# SAMC21_Xplained_Pro_EDBG.net
KiCad netlist of a schematic drawn in Altium Designer
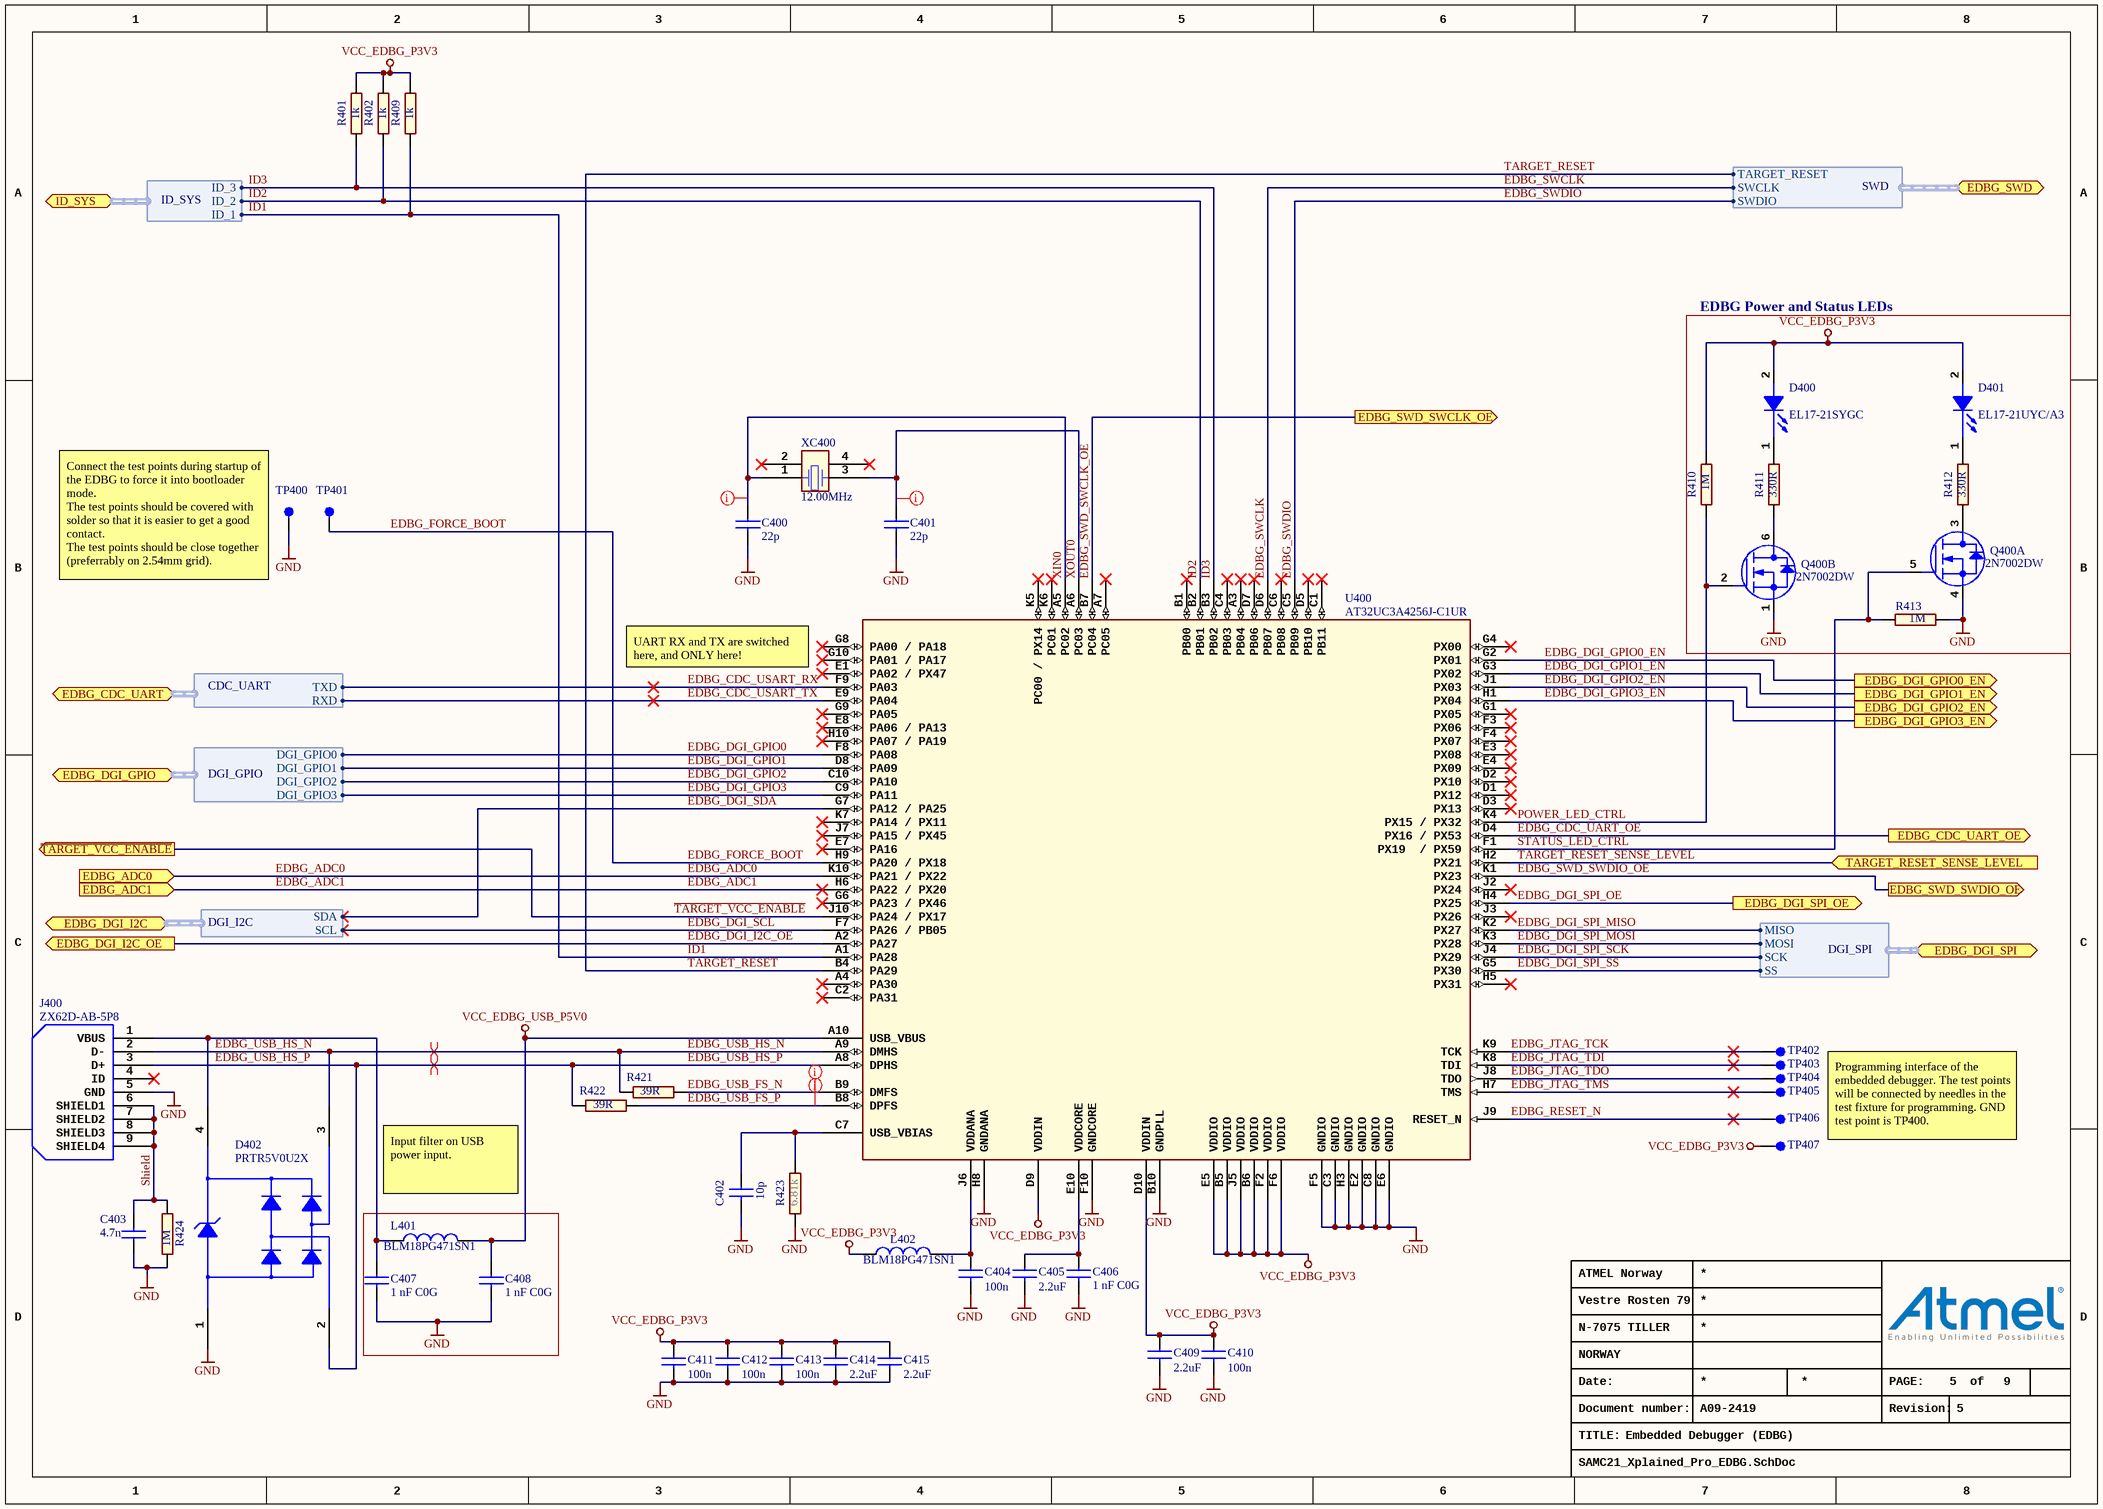
[diagram p0: SAMC21_Xplained_Pro_EDBG.SchDoc]

(export (version "E")
  (design (tool "Eeschema 10.0.6"))
  (components
    (comp (ref "C400")
      (value "22p")
      (footprint "AP1-00053")
      (description "Ceramic capacitor, SMD 0402, NP0, 50V, +/-5%")
      (fields (field (name "TOLERANCE") "50V, +/-5%"))
      (libsource (lib "AltiumDbLib") (part "CAP-NONPOL"))
    )
    (comp (ref "C401")
      (value "22p")
      (footprint "AP1-00053")
      (description "Ceramic capacitor, SMD 0402, NP0, 50V, +/-5%")
      (fields (field (name "TOLERANCE") "50V, +/-5%"))
      (libsource (lib "AltiumDbLib") (part "CAP-NONPOL"))
    )
    (comp (ref "C402")
      (value "10p")
      (footprint "AP1-00053")
      (description "Ceramic capacitor, SMD 0402, NP0, 50V, +/-5%")
      (fields (field (name "TOLERANCE") "50V, +/-5%"))
      (libsource (lib "AltiumDbLib") (part "CAP-NONPOL"))
    )
    (comp (ref "C403")
      (value "4.7n")
      (footprint "AP1-00053")
      (description "Ceramic capacitor, SMD 0402, X7R, 25V, +/-10%")
      (fields (field (name "TOLERANCE") "25V, +/-10%"))
      (libsource (lib "AltiumDbLib") (part "CAP-NONPOL"))
    )
    (comp (ref "C404")
      (value "100n")
      (footprint "AP1-00053")
      (description "Ceramic capacitor, SMD 0402, X7R, 16V, +/-10%")
      (fields (field (name "TOLERANCE") "16V, +/-10%") (field (name "MANUFACTURER") "Kemet"))
      (libsource (lib "AltiumDbLib") (part "CAP-NONPOL"))
    )
    (comp (ref "C405")
      (value "2.2uF")
      (footprint "AP1-00053")
      (description "Ceramic capacitor, SMD 0402, X5R, 6.3V, +/-20%")
      (fields (field (name "TOLERANCE") "Â±20%") (field (name "MANUFACTURER") "Kemet"))
      (libsource (lib "AltiumDbLib") (part "CAP-NONPOL"))
    )
    (comp (ref "C406")
      (value "1 nF C0G")
      (footprint "AP1-00053")
      (description "Ceramic capacitor, SMD 0402, C0G, 50V, +/-5%")
      (fields (field (name "TOLERANCE") "5%") (field (name "MANUFACTURER") "Murata"))
      (libsource (lib "AltiumDbLib") (part "CAP-NONPOL"))
    )
    (comp (ref "C407")
      (value "1 nF C0G")
      (footprint "AP1-00053")
      (description "Ceramic capacitor, SMD 0402, C0G, 50V, +/-5%")
      (fields (field (name "TOLERANCE") "5%") (field (name "MANUFACTURER") "Murata"))
      (libsource (lib "AltiumDbLib") (part "CAP-NONPOL"))
    )
    (comp (ref "C408")
      (value "1 nF C0G")
      (footprint "AP1-00053")
      (description "Ceramic capacitor, SMD 0402, C0G, 50V, +/-5%")
      (fields (field (name "TOLERANCE") "5%") (field (name "MANUFACTURER") "Murata"))
      (libsource (lib "AltiumDbLib") (part "CAP-NONPOL"))
    )
    (comp (ref "C409")
      (value "2.2uF")
      (footprint "AP1-00053")
      (description "Ceramic capacitor, SMD 0402, X5R, 6.3V, +/-20%")
      (fields (field (name "TOLERANCE") "Â±20%") (field (name "MANUFACTURER") "Kemet"))
      (libsource (lib "AltiumDbLib") (part "CAP-NONPOL"))
    )
    (comp (ref "C410")
      (value "100n")
      (footprint "AP1-00053")
      (description "Ceramic capacitor, SMD 0402, X7R, 16V, +/-10%")
      (fields (field (name "TOLERANCE") "16V, +/-10%") (field (name "MANUFACTURER") "Kemet"))
      (libsource (lib "AltiumDbLib") (part "CAP-NONPOL"))
    )
    (comp (ref "C411")
      (value "100n")
      (footprint "AP1-00053")
      (description "Ceramic capacitor, SMD 0402, X7R, 16V, +/-10%")
      (fields (field (name "TOLERANCE") "16V, +/-10%") (field (name "MANUFACTURER") "Kemet"))
      (libsource (lib "AltiumDbLib") (part "CAP-NONPOL"))
    )
    (comp (ref "C412")
      (value "100n")
      (footprint "AP1-00053")
      (description "Ceramic capacitor, SMD 0402, X7R, 16V, +/-10%")
      (fields (field (name "TOLERANCE") "16V, +/-10%") (field (name "MANUFACTURER") "Kemet"))
      (libsource (lib "AltiumDbLib") (part "CAP-NONPOL"))
    )
    (comp (ref "C413")
      (value "100n")
      (footprint "AP1-00053")
      (description "Ceramic capacitor, SMD 0402, X7R, 16V, +/-10%")
      (fields (field (name "TOLERANCE") "16V, +/-10%") (field (name "MANUFACTURER") "Kemet"))
      (libsource (lib "AltiumDbLib") (part "CAP-NONPOL"))
    )
    (comp (ref "C414")
      (value "2.2uF")
      (footprint "AP1-00053")
      (description "Ceramic capacitor, SMD 0402, X5R, 6.3V, +/-20%")
      (fields (field (name "TOLERANCE") "Â±20%") (field (name "MANUFACTURER") "Kemet"))
      (libsource (lib "AltiumDbLib") (part "CAP-NONPOL"))
    )
    (comp (ref "C415")
      (value "2.2uF")
      (footprint "AP1-00053")
      (description "Ceramic capacitor, SMD 0402, X5R, 6.3V, +/-20%")
      (fields (field (name "TOLERANCE") "Â±20%") (field (name "MANUFACTURER") "Kemet"))
      (libsource (lib "AltiumDbLib") (part "CAP-NONPOL"))
    )
    (comp (ref "D400")
      (value "EL17-21SYGC")
      (footprint "AP4-00013")
      (description "LED, Green, Wave length=575nm, SMD 0805, ±70°")
      (fields (field (name "MANUFACTURER") "Everlight"))
      (libsource (lib "AltiumDbLib") (part "LED_12"))
    )
    (comp (ref "D401")
      (value "EL17-21UYC/A3")
      (footprint "AP4-00013")
      (description "LED, Yellow, Wave length=591nm, SMD 0805, ±70°")
      (fields (field (name "MANUFACTURER") "Everlight") (field (name "MPN") "17-21UYC/S530-A3/TR8"))
      (libsource (lib "AltiumDbLib") (part "LED_12"))
    )
    (comp (ref "D402")
      (value "PRTR5V0U2X")
      (footprint "AP4-00001")
      (description "Double rail-to-rail USB ESD protection diode")
      (fields
        (field (name "MANUFACTURER") "NXP")
        (field (name "Comment") "Changed manufacturer from Philips to NXP.")
      )
      (libsource (lib "AltiumDbLib") (part "PRTR5V0U2X"))
    )
    (comp (ref "J400")
      (value "ZX62D-AB-5P8")
      (footprint "AP8-00852")
      (description "Micro USB AB Connector, Standard SMT + DIP")
      (fields (field (name "MANUFACTURER") "HIROSE") (field (name "Comment") "2,000 pieces per reel"))
      (libsource (lib "AltiumDbLib") (part "USB_AB"))
    )
    (comp (ref "L401")
      (value "BLM18PG471SN1")
      (footprint "AP3-00005")
      (description "SMD RF inductor 0603. Z=470Ohm (@100MHz), Max R(dc)=0.65Ohm, Max current=1A")
      (fields (field (name "TOLERANCE") "±25%") (field (name "MANUFACTURER") "Murata"))
      (libsource (lib "AltiumDbLib") (part "INDUCTOR"))
    )
    (comp (ref "L402")
      (value "BLM18PG471SN1")
      (footprint "AP3-00005")
      (description "SMD RF inductor 0603. Z=470Ohm (@100MHz), Max R(dc)=0.65Ohm, Max current=1A")
      (fields (field (name "TOLERANCE") "±25%") (field (name "MANUFACTURER") "Murata"))
      (libsource (lib "AltiumDbLib") (part "INDUCTOR"))
    )
    (comp (ref "Q400")
      (value "2N7002DW")
      (footprint "AP5-00001")
      (description "Dual N-Channel MOSFET, 60V, 115mA cont,RDS(ON) < 7.5 Ohm @50mA@5V, SOT-363")
      (fields
        (field (name "MANUFACTURER") "Fairchild")
        (field (name "Comment") "Same as 2N7002 but with two MOSFETs in one package")
      )
      (libsource (lib "AltiumDbLib") (part "MOSFET_DUAL_N_S2G2D1S1G1D2"))
    )
    (comp (ref "R401")
      (value "1k")
      (footprint "AP2-00000")
      (description "Thick film resistor, SMD 0402, 1/16W, 1%")
      (fields (field (name "TOLERANCE") "1 %"))
      (libsource (lib "") (part "R2_1"))
    )
    (comp (ref "R402")
      (value "1k")
      (footprint "AP2-00000")
      (description "Thick film resistor, SMD 0402, 1/16W, 1%")
      (fields (field (name "TOLERANCE") "1 %"))
      (libsource (lib "") (part "R2_1"))
    )
    (comp (ref "R409")
      (value "1k")
      (footprint "AP2-00000")
      (description "Thick film resistor, SMD 0402, 1/16W, 1%")
      (fields (field (name "TOLERANCE") "1 %"))
      (libsource (lib "") (part "R2_1"))
    )
    (comp (ref "R410")
      (value "1M")
      (footprint "AP2-00000")
      (description "Thick film resistor, SMD 0402, 1/16W, 1%")
      (fields (field (name "TOLERANCE") "1 %"))
      (libsource (lib "") (part "R2_1"))
    )
    (comp (ref "R411")
      (value "330R")
      (footprint "AP2-00000")
      (description "Thick film resistor, SMD 0402, 1/16W, 1%")
      (fields (field (name "TOLERANCE") "1 %"))
      (libsource (lib "") (part "R2_1"))
    )
    (comp (ref "R412")
      (value "330R")
      (footprint "AP2-00000")
      (description "Thick film resistor, SMD 0402, 1/16W, 1%")
      (fields (field (name "TOLERANCE") "1 %"))
      (libsource (lib "") (part "R2_1"))
    )
    (comp (ref "R413")
      (value "1M")
      (footprint "AP2-00000")
      (description "Thick film resistor, SMD 0402, 1/16W, 1%")
      (fields (field (name "TOLERANCE") "1 %"))
      (libsource (lib "") (part "R2_2"))
    )
    (comp (ref "R421")
      (value "39R")
      (footprint "AP2-00011")
      (description "Thick film resistor, SMD 0402, 1/16W, 1%")
      (fields (field (name "TOLERANCE") "1 %"))
      (libsource (lib "AltiumDbLib") (part "R2"))
    )
    (comp (ref "R422")
      (value "39R")
      (footprint "AP2-00011")
      (description "Thick film resistor, SMD 0402, 1/16W, 1%")
      (fields (field (name "TOLERANCE") "1 %"))
      (libsource (lib "AltiumDbLib") (part "R2"))
    )
    (comp (ref "R423")
      (value "6.81k")
      (footprint "AP2-00011")
      (description "Thick film resistor, SMD 0402, 1/16W, 1%")
      (fields (field (name "TOLERANCE") "1%"))
      (libsource (lib "") (part "R2_1"))
    )
    (comp (ref "R424")
      (value "1M")
      (footprint "AP2-00011")
      (description "Thick film resistor, SMD 0402, 1/16W, 1%")
      (fields (field (name "TOLERANCE") "1 %"))
      (libsource (lib "") (part "R2_3"))
    )
    (comp (ref "TP400")
      (value "~")
      (footprint "AP8-00010")
      (description "Single SMD testpad")
      (libsource (lib "AltiumDbLib") (part "TESTPOINT"))
    )
    (comp (ref "TP401")
      (value "~")
      (footprint "AP8-00010")
      (description "Single SMD testpad")
      (libsource (lib "AltiumDbLib") (part "TESTPOINT"))
    )
    (comp (ref "TP402")
      (value "~")
      (footprint "AP8-00010")
      (description "Single SMD testpad")
      (libsource (lib "AltiumDbLib") (part "TESTPOINT"))
    )
    (comp (ref "TP403")
      (value "~")
      (footprint "AP8-00010")
      (description "Single SMD testpad")
      (libsource (lib "AltiumDbLib") (part "TESTPOINT"))
    )
    (comp (ref "TP404")
      (value "~")
      (footprint "AP8-00010")
      (description "Single SMD testpad")
      (libsource (lib "AltiumDbLib") (part "TESTPOINT"))
    )
    (comp (ref "TP405")
      (value "~")
      (footprint "AP8-00010")
      (description "Single SMD testpad")
      (libsource (lib "AltiumDbLib") (part "TESTPOINT"))
    )
    (comp (ref "TP406")
      (value "~")
      (footprint "AP8-00010")
      (description "Single SMD testpad")
      (libsource (lib "AltiumDbLib") (part "TESTPOINT"))
    )
    (comp (ref "TP407")
      (value "~")
      (footprint "AP8-00010")
      (description "Single SMD testpad")
      (libsource (lib "AltiumDbLib") (part "TESTPOINT"))
    )
    (comp (ref "U400")
      (value "AT32UC3A4256J-C1UR")
      (footprint "AP6-00206")
      (description "AVR 32-bit RISC MCU")
      (fields (field (name "MANUFACTURER") "ATMEL") (field (name "Comment") "100 ball VFBGA"))
      (libsource (lib "AltiumDbLib") (part "AT32UC3A4_VFBGA"))
    )
    (comp (ref "XC400")
      (value "12.00MHz")
      (footprint "AP7-00039")
      (description "Fox FQ5032B 12.0MHz SMD crystal 738B-12")
      (fields (field (name "TOLERANCE") "Â±30ppm") (field (name "MANUFACTURER") "Fox  Electronics"))
      (libsource (lib "AltiumDbLib") (part "CRYSTAL1324"))
    )
  )
  (nets
    (net (code "7") (name "/EDBG_ADC0") (class "Default")
      (node (ref "U400") (pin "K10") (pinfunction "PA21_/_PX22_K10") (pintype "bidirectional"))
    )
    (net (code "8") (name "/EDBG_ADC1") (class "Default")
      (node (ref "U400") (pin "H6") (pinfunction "PA22_/_PX20_H6") (pintype "bidirectional+no_connect"))
    )
    (net (code "9") (name "/EDBG_CDC_UART_OE") (class "Default")
      (node (ref "U400") (pin "D4") (pinfunction "PX16_/_PX53_D4") (pintype "bidirectional"))
    )
    (net (code "10") (name "/EDBG_CDC_USART_RX") (class "Default")
      (node (ref "U400") (pin "F9") (pinfunction "PA03_F9") (pintype "bidirectional"))
    )
    (net (code "11") (name "/EDBG_CDC_USART_TX") (class "Default")
      (node (ref "U400") (pin "E9") (pinfunction "PA04_E9") (pintype "bidirectional"))
    )
    (net (code "12") (name "/EDBG_DGI_GPIO0") (class "Default")
      (node (ref "U400") (pin "F8") (pinfunction "PA08_F8") (pintype "bidirectional"))
    )
    (net (code "13") (name "/EDBG_DGI_GPIO0_EN") (class "Default")
      (node (ref "U400") (pin "G2") (pinfunction "PX01_G2") (pintype "bidirectional"))
    )
    (net (code "14") (name "/EDBG_DGI_GPIO1") (class "Default")
      (node (ref "U400") (pin "D8") (pinfunction "PA09_D8") (pintype "bidirectional"))
    )
    (net (code "15") (name "/EDBG_DGI_GPIO1_EN") (class "Default")
      (node (ref "U400") (pin "G3") (pinfunction "PX02_G3") (pintype "bidirectional"))
    )
    (net (code "16") (name "/EDBG_DGI_GPIO2") (class "Default")
      (node (ref "U400") (pin "C10") (pinfunction "PA10_C10") (pintype "bidirectional"))
    )
    (net (code "17") (name "/EDBG_DGI_GPIO2_EN") (class "Default")
      (node (ref "U400") (pin "J1") (pinfunction "PX03_J1") (pintype "bidirectional"))
    )
    (net (code "18") (name "/EDBG_DGI_GPIO3") (class "Default")
      (node (ref "U400") (pin "C9") (pinfunction "PA11_C9") (pintype "bidirectional"))
    )
    (net (code "19") (name "/EDBG_DGI_GPIO3_EN") (class "Default")
      (node (ref "U400") (pin "H1") (pinfunction "PX04_H1") (pintype "bidirectional"))
    )
    (net (code "20") (name "/EDBG_DGI_I2C_OE") (class "Default")
      (node (ref "U400") (pin "A2") (pinfunction "PA27_A2") (pintype "bidirectional"))
    )
    (net (code "21") (name "/EDBG_DGI_SCL") (class "Default")
      (node (ref "U400") (pin "F7") (pinfunction "PA26_/_PB05_F7") (pintype "bidirectional+no_connect"))
    )
    (net (code "22") (name "/EDBG_DGI_SDA") (class "Default")
      (node (ref "U400") (pin "G7") (pinfunction "PA12_/_PA25_G7") (pintype "bidirectional+no_connect"))
    )
    (net (code "23") (name "/EDBG_DGI_SPI_MISO") (class "Default")
      (node (ref "U400") (pin "K2") (pinfunction "PX27_K2") (pintype "bidirectional"))
    )
    (net (code "24") (name "/EDBG_DGI_SPI_MOSI") (class "Default")
      (node (ref "U400") (pin "K3") (pinfunction "PX28_K3") (pintype "bidirectional"))
    )
    (net (code "25") (name "/EDBG_DGI_SPI_OE") (class "Default")
      (node (ref "U400") (pin "H4") (pinfunction "PX25_H4") (pintype "bidirectional"))
    )
    (net (code "26") (name "/EDBG_DGI_SPI_SCK") (class "Default")
      (node (ref "U400") (pin "J4") (pinfunction "PX29_J4") (pintype "bidirectional"))
    )
    (net (code "27") (name "/EDBG_DGI_SPI_SS") (class "Default")
      (node (ref "U400") (pin "G5") (pinfunction "PX30_G5") (pintype "bidirectional"))
    )
    (net (code "28") (name "/EDBG_FORCE_BOOT") (class "Default")
      (node (ref "TP401") (pin "1") (pinfunction "1_1") (pintype "passive"))
      (node (ref "U400") (pin "H9") (pinfunction "PA20_/_PX18_H9") (pintype "bidirectional"))
    )
    (net (code "29") (name "/EDBG_JTAG_TCK") (class "Default")
      (node (ref "TP402") (pin "1") (pinfunction "1_1") (pintype "passive"))
      (node (ref "U400") (pin "K9") (pinfunction "TCK_K9") (pintype "input"))
    )
    (net (code "30") (name "/EDBG_JTAG_TDI") (class "Default")
      (node (ref "TP403") (pin "1") (pinfunction "1_1") (pintype "passive"))
      (node (ref "U400") (pin "K8") (pinfunction "TDI_K8") (pintype "input"))
    )
    (net (code "31") (name "/EDBG_JTAG_TDO") (class "Default")
      (node (ref "TP404") (pin "1") (pinfunction "1_1") (pintype "passive"))
      (node (ref "U400") (pin "J8") (pinfunction "TDO_J8") (pintype "output"))
    )
    (net (code "32") (name "/EDBG_JTAG_TMS") (class "Default")
      (node (ref "TP405") (pin "1") (pinfunction "1_1") (pintype "passive"))
      (node (ref "U400") (pin "H7") (pinfunction "TMS_H7") (pintype "input"))
    )
    (net (code "33") (name "/EDBG_RESET_N") (class "Default")
      (node (ref "TP406") (pin "1") (pinfunction "1_1") (pintype "passive"))
      (node (ref "U400") (pin "J9") (pinfunction "RESET_N_J9") (pintype "input"))
    )
    (net (code "34") (name "/EDBG_SWCLK") (class "Default")
      (node (ref "U400") (pin "D6") (pinfunction "PB07_D6") (pintype "bidirectional"))
    )
    (net (code "35") (name "/EDBG_SWDIO") (class "Default")
      (node (ref "U400") (pin "C5") (pinfunction "PB09_C5") (pintype "bidirectional"))
    )
    (net (code "36") (name "/EDBG_SWD_SWCLK_OE") (class "Default")
      (node (ref "U400") (pin "B7") (pinfunction "PC04_B7") (pintype "bidirectional"))
    )
    (net (code "37") (name "/EDBG_SWD_SWDIO_OE") (class "Default")
      (node (ref "U400") (pin "K1") (pinfunction "PX23_K1") (pintype "bidirectional"))
    )
    (net (code "38") (name "/EDBG_USB_FS_N") (class "Default")
      (node (ref "R421") (pin "2") (pinfunction "2_2") (pintype "passive"))
      (node (ref "U400") (pin "B9") (pinfunction "DMFS_B9") (pintype "bidirectional"))
    )
    (net (code "39") (name "/EDBG_USB_FS_P") (class "Default")
      (node (ref "R422") (pin "2") (pinfunction "2_2") (pintype "passive"))
      (node (ref "U400") (pin "B8") (pinfunction "DPFS_B8") (pintype "bidirectional"))
    )
    (net (code "40") (name "/EDBG_USB_HS_N") (class "Default")
      (node (ref "D402") (pin "3") (pinfunction "I/O_2_3") (pintype "passive"))
      (node (ref "J400") (pin "2") (pinfunction "D-_2") (pintype "passive"))
      (node (ref "R421") (pin "1") (pinfunction "1_1") (pintype "passive"))
      (node (ref "U400") (pin "A9") (pinfunction "DMHS_A9") (pintype "bidirectional"))
    )
    (net (code "41") (name "/EDBG_USB_HS_P") (class "Default")
      (node (ref "D402") (pin "2") (pinfunction "I/O_1_2") (pintype "passive"))
      (node (ref "J400") (pin "3") (pinfunction "D+_3") (pintype "passive"))
      (node (ref "R422") (pin "1") (pinfunction "1_1") (pintype "passive"))
      (node (ref "U400") (pin "A8") (pinfunction "DPHS_A8") (pintype "bidirectional"))
    )
    (net (code "42") (name "/ID1") (class "Default")
      (node (ref "R409") (pin "1") (pinfunction "1_1") (pintype "passive"))
      (node (ref "U400") (pin "A1") (pinfunction "PA28_A1") (pintype "bidirectional"))
    )
    (net (code "43") (name "/ID2") (class "Default")
      (node (ref "R402") (pin "1") (pinfunction "1_1") (pintype "passive"))
      (node (ref "U400") (pin "B2") (pinfunction "PB01_B2") (pintype "bidirectional"))
    )
    (net (code "44") (name "/ID3") (class "Default")
      (node (ref "R401") (pin "1") (pinfunction "1_1") (pintype "passive"))
      (node (ref "U400") (pin "B3") (pinfunction "PB02_B3") (pintype "bidirectional"))
    )
    (net (code "45") (name "/POWER_LED_CTRL") (class "Default")
      (node (ref "Q400") (pin "2") (pinfunction "G2_2") (pintype "passive"))
      (node (ref "R410") (pin "1") (pinfunction "1_1") (pintype "passive"))
      (node (ref "U400") (pin "K4") (pinfunction "PX15_/_PX32_K4") (pintype "bidirectional"))
    )
    (net (code "46") (name "/STATUS_LED_CTRL") (class "Default")
      (node (ref "Q400") (pin "5") (pinfunction "G1_5") (pintype "passive"))
      (node (ref "R413") (pin "2") (pinfunction "2_2") (pintype "passive"))
      (node (ref "U400") (pin "F1") (pinfunction "PX19__/_PX59_F1") (pintype "bidirectional"))
    )
    (net (code "47") (name "/Shield") (class "Default")
      (node (ref "C403") (pin "2") (pinfunction "2_2") (pintype "passive"))
      (node (ref "J400") (pin "6") (pinfunction "SHIELD1_6") (pintype "passive"))
      (node (ref "J400") (pin "7") (pinfunction "SHIELD2_7") (pintype "passive"))
      (node (ref "J400") (pin "8") (pinfunction "SHIELD3_8") (pintype "passive"))
      (node (ref "J400") (pin "9") (pinfunction "SHIELD4_9") (pintype "passive"))
      (node (ref "R424") (pin "2") (pinfunction "2_2") (pintype "passive"))
    )
    (net (code "48") (name "/TARGET_RESET") (class "Default")
      (node (ref "U400") (pin "B4") (pinfunction "PA29_B4") (pintype "bidirectional"))
    )
    (net (code "49") (name "/TARGET_RESET_SENSE_LEVEL") (class "Default")
      (node (ref "U400") (pin "H2") (pinfunction "PX21_H2") (pintype "bidirectional"))
    )
    (net (code "50") (name "/XIN0") (class "Default")
      (node (ref "C400") (pin "1") (pinfunction "1_1") (pintype "passive"))
      (node (ref "U400") (pin "A5") (pinfunction "PC02_A5") (pintype "bidirectional"))
      (node (ref "XC400") (pin "1") (pinfunction "1_1") (pintype "passive"))
    )
    (net (code "51") (name "/XOUT0") (class "Default")
      (node (ref "C401") (pin "1") (pinfunction "1_1") (pintype "passive"))
      (node (ref "U400") (pin "A6") (pinfunction "PC03_A6") (pintype "bidirectional"))
      (node (ref "XC400") (pin "3") (pinfunction "3_3") (pintype "passive"))
    )
    (net (code "58") (name "/~{TARGET_VCC_ENABLE}") (class "Default")
      (node (ref "U400") (pin "J10") (pinfunction "PA24_/_PX17_J10") (pintype "bidirectional"))
    )
    (net (code "59") (name "GND") (class "Default")
      (node (ref "C400") (pin "2") (pinfunction "2_2") (pintype "passive"))
      (node (ref "C401") (pin "2") (pinfunction "2_2") (pintype "passive"))
      (node (ref "C402") (pin "2") (pinfunction "2_2") (pintype "passive"))
      (node (ref "C403") (pin "1") (pinfunction "1_1") (pintype "passive"))
      (node (ref "C404") (pin "2") (pinfunction "2_2") (pintype "passive"))
      (node (ref "C405") (pin "2") (pinfunction "2_2") (pintype "passive"))
      (node (ref "C406") (pin "2") (pinfunction "2_2") (pintype "passive"))
      (node (ref "C407") (pin "2") (pinfunction "2_2") (pintype "passive"))
      (node (ref "C408") (pin "2") (pinfunction "2_2") (pintype "passive"))
      (node (ref "C409") (pin "2") (pinfunction "2_2") (pintype "passive"))
      (node (ref "C410") (pin "2") (pinfunction "2_2") (pintype "passive"))
      (node (ref "C411") (pin "2") (pinfunction "2_2") (pintype "passive"))
      (node (ref "C412") (pin "2") (pinfunction "2_2") (pintype "passive"))
      (node (ref "C413") (pin "2") (pinfunction "2_2") (pintype "passive"))
      (node (ref "C414") (pin "2") (pinfunction "2_2") (pintype "passive"))
      (node (ref "C415") (pin "2") (pinfunction "2_2") (pintype "passive"))
      (node (ref "D402") (pin "1") (pinfunction "GND_1") (pintype "passive"))
      (node (ref "J400") (pin "5") (pinfunction "GND_5") (pintype "passive"))
      (node (ref "Q400") (pin "1") (pinfunction "S2_1") (pintype "passive"))
      (node (ref "Q400") (pin "4") (pinfunction "S1_4") (pintype "passive"))
      (node (ref "R413") (pin "1") (pinfunction "1_1") (pintype "passive"))
      (node (ref "R423") (pin "1") (pinfunction "1_1") (pintype "passive"))
      (node (ref "R424") (pin "1") (pinfunction "1_1") (pintype "passive"))
      (node (ref "TP400") (pin "1") (pinfunction "1_1") (pintype "passive"))
      (node (ref "U400") (pin "B10") (pinfunction "GNDPLL_B10") (pintype "power_in"))
      (node (ref "U400") (pin "C3") (pinfunction "GNDIO_C3") (pintype "power_in"))
      (node (ref "U400") (pin "C8") (pinfunction "GNDIO_C8") (pintype "power_in"))
      (node (ref "U400") (pin "E2") (pinfunction "GNDIO_E2") (pintype "power_in"))
      (node (ref "U400") (pin "E6") (pinfunction "GNDIO_E6") (pintype "power_in"))
      (node (ref "U400") (pin "F10") (pinfunction "GNDCORE_F10") (pintype "power_in"))
      (node (ref "U400") (pin "F5") (pinfunction "GNDIO_F5") (pintype "power_in"))
      (node (ref "U400") (pin "H3") (pinfunction "GNDIO_H3") (pintype "power_in"))
      (node (ref "U400") (pin "H8") (pinfunction "GNDANA_H8") (pintype "power_in"))
    )
    (net (code "60") (name "Net-(D400-CATHODE)") (class "Default")
      (node (ref "D400") (pin "1") (pinfunction "CATHODE_1") (pintype "passive"))
      (node (ref "R411") (pin "2") (pinfunction "2_2") (pintype "passive"))
    )
    (net (code "61") (name "Net-(D401-CATHODE)") (class "Default")
      (node (ref "D401") (pin "1") (pinfunction "CATHODE_1") (pintype "passive"))
      (node (ref "R412") (pin "2") (pinfunction "2_2") (pintype "passive"))
    )
    (net (code "62") (name "Net-(D402-VCC)") (class "Default")
      (node (ref "C407") (pin "1") (pinfunction "1_1") (pintype "passive"))
      (node (ref "D402") (pin "4") (pinfunction "VCC_4") (pintype "passive"))
      (node (ref "J400") (pin "1") (pinfunction "VBUS_1") (pintype "passive"))
      (node (ref "L401") (pin "1") (pinfunction "1_1") (pintype "passive"))
    )
    (net (code "63") (name "Net-(Q400A-D1)") (class "Default")
      (node (ref "Q400") (pin "3") (pinfunction "D1_3") (pintype "passive"))
      (node (ref "R412") (pin "1") (pinfunction "1_1") (pintype "passive"))
    )
    (net (code "64") (name "Net-(Q400B-D2)") (class "Default")
      (node (ref "Q400") (pin "6") (pinfunction "D2_6") (pintype "passive"))
      (node (ref "R411") (pin "1") (pinfunction "1_1") (pintype "passive"))
    )
    (net (code "65") (name "Net-(U400-USB_VBIAS)") (class "Default")
      (node (ref "C402") (pin "1") (pinfunction "1_1") (pintype "passive"))
      (node (ref "R423") (pin "2") (pinfunction "2_2") (pintype "passive"))
      (node (ref "U400") (pin "C7") (pinfunction "USB_VBIAS_C7") (pintype "power_in"))
    )
    (net (code "66") (name "Net-(U400-VDDANA)") (class "Default")
      (node (ref "C404") (pin "1") (pinfunction "1_1") (pintype "passive"))
      (node (ref "L402") (pin "2") (pinfunction "2_2") (pintype "passive"))
      (node (ref "U400") (pin "J6") (pinfunction "VDDANA_J6") (pintype "power_in"))
    )
    (net (code "67") (name "Net-(U400-VDDCORE)") (class "Default")
      (node (ref "C405") (pin "1") (pinfunction "1_1") (pintype "passive"))
      (node (ref "C406") (pin "1") (pinfunction "1_1") (pintype "passive"))
      (node (ref "U400") (pin "E10") (pinfunction "VDDCORE_E10") (pintype "power_in"))
    )
    (net (code "68") (name "VCC_EDBG_P3V3") (class "Default")
      (node (ref "C409") (pin "1") (pinfunction "1_1") (pintype "passive"))
      (node (ref "C410") (pin "1") (pinfunction "1_1") (pintype "passive"))
      (node (ref "C411") (pin "1") (pinfunction "1_1") (pintype "passive"))
      (node (ref "C412") (pin "1") (pinfunction "1_1") (pintype "passive"))
      (node (ref "C413") (pin "1") (pinfunction "1_1") (pintype "passive"))
      (node (ref "C414") (pin "1") (pinfunction "1_1") (pintype "passive"))
      (node (ref "C415") (pin "1") (pinfunction "1_1") (pintype "passive"))
      (node (ref "D400") (pin "2") (pinfunction "ANODE_2") (pintype "passive"))
      (node (ref "D401") (pin "2") (pinfunction "ANODE_2") (pintype "passive"))
      (node (ref "L402") (pin "1") (pinfunction "1_1") (pintype "passive"))
      (node (ref "R401") (pin "2") (pinfunction "2_2") (pintype "passive"))
      (node (ref "R402") (pin "2") (pinfunction "2_2") (pintype "passive"))
      (node (ref "R409") (pin "2") (pinfunction "2_2") (pintype "passive"))
      (node (ref "R410") (pin "2") (pinfunction "2_2") (pintype "passive"))
      (node (ref "TP407") (pin "1") (pinfunction "1_1") (pintype "passive"))
      (node (ref "U400") (pin "B5") (pinfunction "VDDIO_B5") (pintype "power_in"))
      (node (ref "U400") (pin "B6") (pinfunction "VDDIO_B6") (pintype "power_in"))
      (node (ref "U400") (pin "D10") (pinfunction "VDDIN_D10") (pintype "power_in"))
      (node (ref "U400") (pin "D9") (pinfunction "VDDIN_D9") (pintype "power_in"))
      (node (ref "U400") (pin "E5") (pinfunction "VDDIO_E5") (pintype "power_in"))
      (node (ref "U400") (pin "F2") (pinfunction "VDDIO_F2") (pintype "power_in"))
      (node (ref "U400") (pin "F6") (pinfunction "VDDIO_F6") (pintype "power_in"))
      (node (ref "U400") (pin "J5") (pinfunction "VDDIO_J5") (pintype "power_in"))
    )
    (net (code "69") (name "VCC_EDBG_USB_P5V0") (class "Default")
      (node (ref "C408") (pin "1") (pinfunction "1_1") (pintype "passive"))
      (node (ref "L401") (pin "2") (pinfunction "2_2") (pintype "passive"))
      (node (ref "U400") (pin "A10") (pinfunction "USB_VBUS_A10") (pintype "power_in"))
    )
    (net (code "70") (name "unconnected-(J400-ID-Pad4)") (class "Default")
      (node (ref "J400") (pin "4") (pinfunction "ID_4") (pintype "passive+no_connect"))
    )
    (net (code "71") (name "unconnected-(U400-PA00_{slash}_PA18-PadG8)") (class "Default")
      (node (ref "U400") (pin "G8") (pinfunction "PA00_/_PA18_G8") (pintype "bidirectional+no_connect"))
    )
    (net (code "72") (name "unconnected-(U400-PA01_{slash}_PA17-PadG10)") (class "Default")
      (node (ref "U400") (pin "G10") (pinfunction "PA01_/_PA17_G10") (pintype "bidirectional+no_connect"))
    )
    (net (code "73") (name "unconnected-(U400-PA02_{slash}_PX47-PadE1)") (class "Default")
      (node (ref "U400") (pin "E1") (pinfunction "PA02_/_PX47_E1") (pintype "bidirectional+no_connect"))
    )
    (net (code "74") (name "unconnected-(U400-PA05-PadG9)") (class "Default")
      (node (ref "U400") (pin "G9") (pinfunction "PA05_G9") (pintype "bidirectional+no_connect"))
    )
    (net (code "75") (name "unconnected-(U400-PA06_{slash}_PA13-PadE8)") (class "Default")
      (node (ref "U400") (pin "E8") (pinfunction "PA06_/_PA13_E8") (pintype "bidirectional+no_connect"))
    )
    (net (code "76") (name "unconnected-(U400-PA07_{slash}_PA19-PadH10)") (class "Default")
      (node (ref "U400") (pin "H10") (pinfunction "PA07_/_PA19_H10") (pintype "bidirectional+no_connect"))
    )
    (net (code "77") (name "unconnected-(U400-PA14_{slash}_PX11-PadK7)") (class "Default")
      (node (ref "U400") (pin "K7") (pinfunction "PA14_/_PX11_K7") (pintype "bidirectional+no_connect"))
    )
    (net (code "78") (name "unconnected-(U400-PA15_{slash}_PX45-PadJ7)") (class "Default")
      (node (ref "U400") (pin "J7") (pinfunction "PA15_/_PX45_J7") (pintype "bidirectional+no_connect"))
    )
    (net (code "79") (name "unconnected-(U400-PA16-PadE7)") (class "Default")
      (node (ref "U400") (pin "E7") (pinfunction "PA16_E7") (pintype "bidirectional+no_connect"))
    )
    (net (code "80") (name "unconnected-(U400-PA23_{slash}_PX46-PadG6)") (class "Default")
      (node (ref "U400") (pin "G6") (pinfunction "PA23_/_PX46_G6") (pintype "bidirectional+no_connect"))
    )
    (net (code "81") (name "unconnected-(U400-PA30-PadA4)") (class "Default")
      (node (ref "U400") (pin "A4") (pinfunction "PA30_A4") (pintype "bidirectional+no_connect"))
    )
    (net (code "82") (name "unconnected-(U400-PA31-PadC2)") (class "Default")
      (node (ref "U400") (pin "C2") (pinfunction "PA31_C2") (pintype "bidirectional+no_connect"))
    )
    (net (code "83") (name "unconnected-(U400-PB00-PadB1)") (class "Default")
      (node (ref "U400") (pin "B1") (pinfunction "PB00_B1") (pintype "bidirectional+no_connect"))
    )
    (net (code "84") (name "unconnected-(U400-PB03-PadC4)") (class "Default")
      (node (ref "U400") (pin "C4") (pinfunction "PB03_C4") (pintype "bidirectional+no_connect"))
    )
    (net (code "85") (name "unconnected-(U400-PB04-PadA3)") (class "Default")
      (node (ref "U400") (pin "A3") (pinfunction "PB04_A3") (pintype "bidirectional+no_connect"))
    )
    (net (code "86") (name "unconnected-(U400-PB06-PadD7)") (class "Default")
      (node (ref "U400") (pin "D7") (pinfunction "PB06_D7") (pintype "bidirectional+no_connect"))
    )
    (net (code "87") (name "unconnected-(U400-PB08-PadC6)") (class "Default")
      (node (ref "U400") (pin "C6") (pinfunction "PB08_C6") (pintype "bidirectional+no_connect"))
    )
    (net (code "88") (name "unconnected-(U400-PB10-PadD5)") (class "Default")
      (node (ref "U400") (pin "D5") (pinfunction "PB10_D5") (pintype "bidirectional+no_connect"))
    )
    (net (code "89") (name "unconnected-(U400-PB11-PadC1)") (class "Default")
      (node (ref "U400") (pin "C1") (pinfunction "PB11_C1") (pintype "bidirectional+no_connect"))
    )
    (net (code "90") (name "unconnected-(U400-PC00_{slash}_PX14-PadK5)") (class "Default")
      (node (ref "U400") (pin "K5") (pinfunction "PC00_/_PX14_K5") (pintype "bidirectional+no_connect"))
    )
    (net (code "91") (name "unconnected-(U400-PC01-PadK6)") (class "Default")
      (node (ref "U400") (pin "K6") (pinfunction "PC01_K6") (pintype "bidirectional+no_connect"))
    )
    (net (code "92") (name "unconnected-(U400-PC05-PadA7)") (class "Default")
      (node (ref "U400") (pin "A7") (pinfunction "PC05_A7") (pintype "bidirectional+no_connect"))
    )
    (net (code "93") (name "unconnected-(U400-PX00-PadG4)") (class "Default")
      (node (ref "U400") (pin "G4") (pinfunction "PX00_G4") (pintype "bidirectional+no_connect"))
    )
    (net (code "94") (name "unconnected-(U400-PX05-PadG1)") (class "Default")
      (node (ref "U400") (pin "G1") (pinfunction "PX05_G1") (pintype "bidirectional+no_connect"))
    )
    (net (code "95") (name "unconnected-(U400-PX06-PadF3)") (class "Default")
      (node (ref "U400") (pin "F3") (pinfunction "PX06_F3") (pintype "bidirectional+no_connect"))
    )
    (net (code "96") (name "unconnected-(U400-PX07-PadF4)") (class "Default")
      (node (ref "U400") (pin "F4") (pinfunction "PX07_F4") (pintype "bidirectional+no_connect"))
    )
    (net (code "97") (name "unconnected-(U400-PX08-PadE3)") (class "Default")
      (node (ref "U400") (pin "E3") (pinfunction "PX08_E3") (pintype "bidirectional+no_connect"))
    )
    (net (code "98") (name "unconnected-(U400-PX09-PadE4)") (class "Default")
      (node (ref "U400") (pin "E4") (pinfunction "PX09_E4") (pintype "bidirectional+no_connect"))
    )
    (net (code "99") (name "unconnected-(U400-PX10-PadD2)") (class "Default")
      (node (ref "U400") (pin "D2") (pinfunction "PX10_D2") (pintype "bidirectional+no_connect"))
    )
    (net (code "100") (name "unconnected-(U400-PX12-PadD1)") (class "Default")
      (node (ref "U400") (pin "D1") (pinfunction "PX12_D1") (pintype "bidirectional+no_connect"))
    )
    (net (code "101") (name "unconnected-(U400-PX13-PadD3)") (class "Default")
      (node (ref "U400") (pin "D3") (pinfunction "PX13_D3") (pintype "bidirectional+no_connect"))
    )
    (net (code "102") (name "unconnected-(U400-PX24-PadJ2)") (class "Default")
      (node (ref "U400") (pin "J2") (pinfunction "PX24_J2") (pintype "bidirectional+no_connect"))
    )
    (net (code "103") (name "unconnected-(U400-PX26-PadJ3)") (class "Default")
      (node (ref "U400") (pin "J3") (pinfunction "PX26_J3") (pintype "bidirectional+no_connect"))
    )
    (net (code "104") (name "unconnected-(U400-PX31-PadH5)") (class "Default")
      (node (ref "U400") (pin "H5") (pinfunction "PX31_H5") (pintype "bidirectional+no_connect"))
    )
    (net (code "105") (name "unconnected-(XC400-Pad2)") (class "Default")
      (node (ref "XC400") (pin "2") (pinfunction "2_2") (pintype "passive+no_connect"))
    )
    (net (code "106") (name "unconnected-(XC400-Pad4)") (class "Default")
      (node (ref "XC400") (pin "4") (pinfunction "4_4") (pintype "passive+no_connect"))
    )
  )
)
